# CAN_new_design.net
KiCad netlist of a schematic drawn in EAGLE
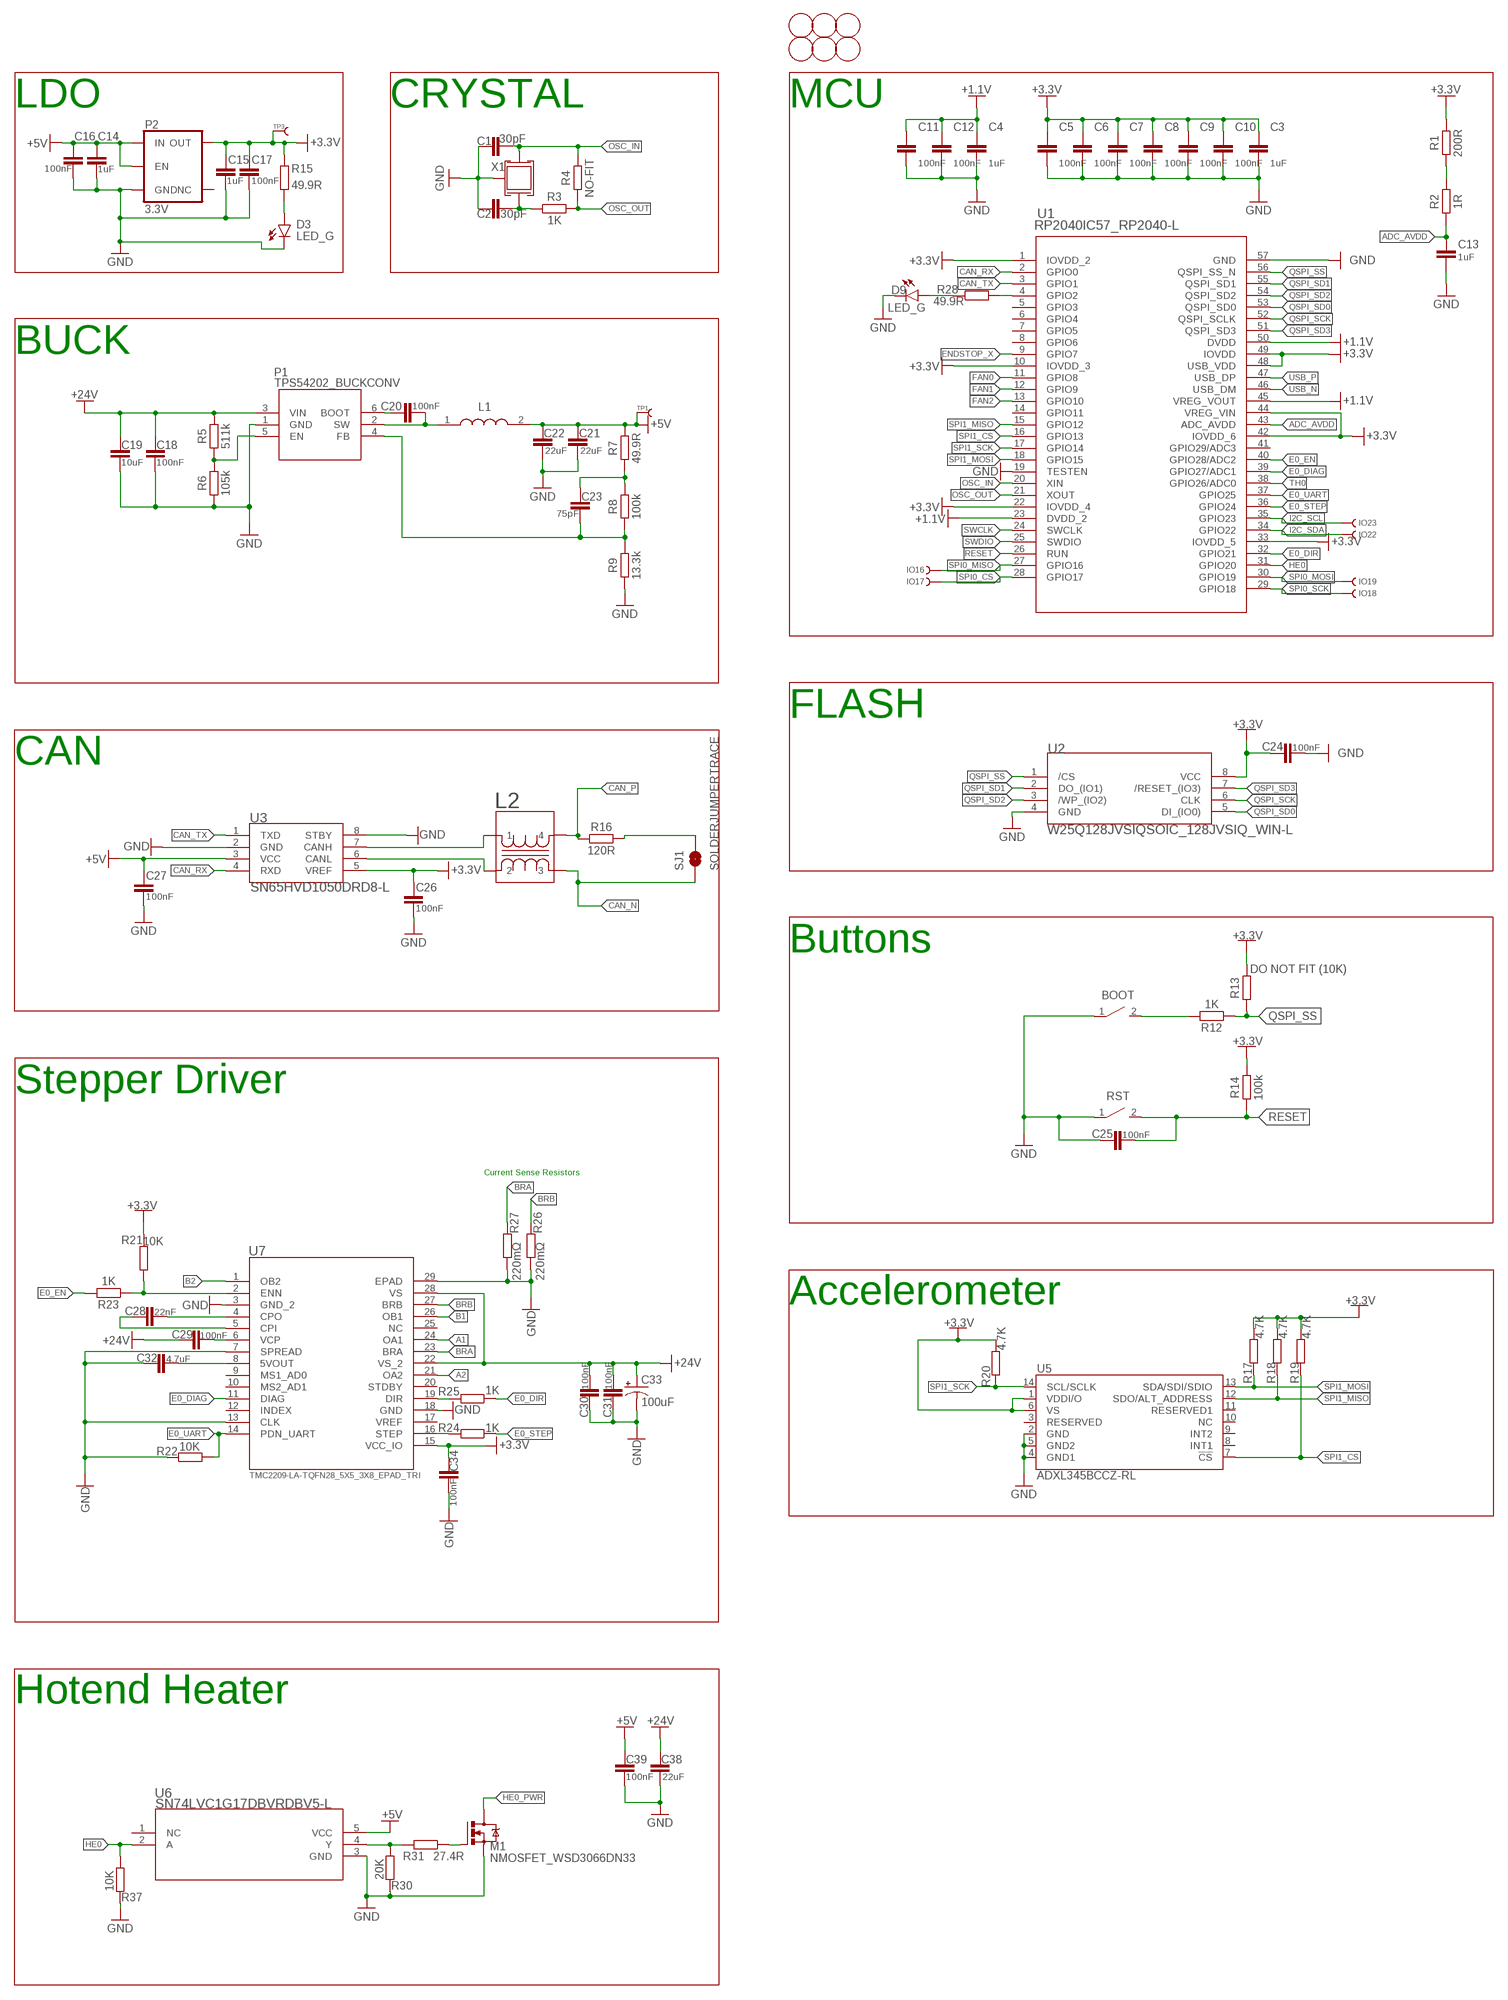
[diagram p0: schematic, sheet 1, part 1 of 2]
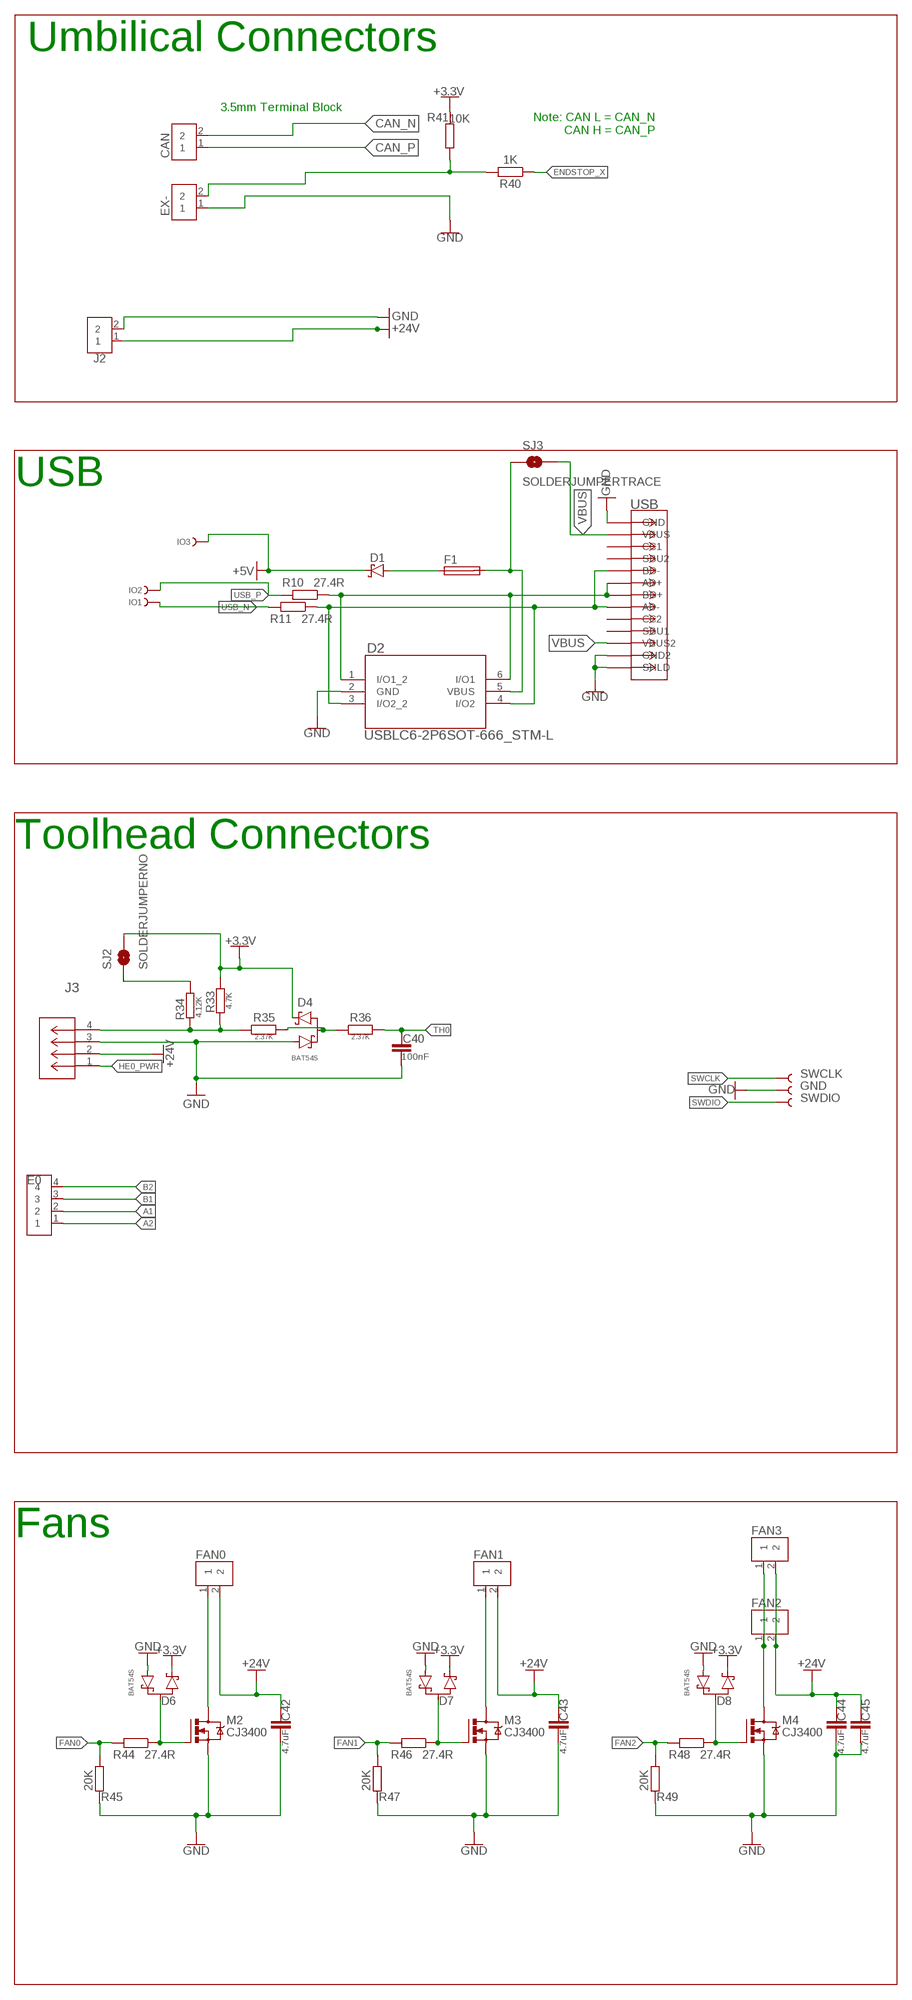
[diagram p1: schematic, sheet 1, part 2 of 2]

(export (version "E")
  (design (tool "Eeschema 10.0.6"))
  (components
    (comp (ref "BOOT")
      (value "B3U-1000P(M)-B")
      (footprint "eagle-import:B3U-1000P(M)-B")
      (fields (field (name "MANUFACTURER") "OMRON"))
      (libsource (lib "eagle-import") (part "B3U-X0001000P(M)-BB3U-1000P(M)-B"))
    )
    (comp (ref "C1")
      (value "30pF")
      (footprint "eagle-import:CAPC1005X60")
      (libsource (lib "eagle-import") (part "CCHIP-0402(1005-METRIC)_"))
    )
    (comp (ref "C2")
      (value "30pF")
      (footprint "eagle-import:CAPC1005X60")
      (libsource (lib "eagle-import") (part "CCHIP-0402(1005-METRIC)_"))
    )
    (comp (ref "C3")
      (value "1uF")
      (footprint "eagle-import:CAPC1005X60")
      (libsource (lib "eagle-import") (part "CCHIP-0402(1005-METRIC)_"))
    )
    (comp (ref "C4")
      (value "1uF")
      (footprint "eagle-import:CAPC1005X60")
      (libsource (lib "eagle-import") (part "CCHIP-0402(1005-METRIC)_"))
    )
    (comp (ref "C5")
      (value "100nF")
      (footprint "eagle-import:CAPC1005X60")
      (libsource (lib "eagle-import") (part "CCHIP-0402(1005-METRIC)_"))
    )
    (comp (ref "C6")
      (value "100nF")
      (footprint "eagle-import:CAPC1005X60")
      (libsource (lib "eagle-import") (part "CCHIP-0402(1005-METRIC)_"))
    )
    (comp (ref "C7")
      (value "100nF")
      (footprint "eagle-import:CAPC1005X60")
      (libsource (lib "eagle-import") (part "CCHIP-0402(1005-METRIC)_"))
    )
    (comp (ref "C8")
      (value "100nF")
      (footprint "eagle-import:CAPC1005X60")
      (libsource (lib "eagle-import") (part "CCHIP-0402(1005-METRIC)_"))
    )
    (comp (ref "C9")
      (value "100nF")
      (footprint "eagle-import:CAPC1005X60")
      (libsource (lib "eagle-import") (part "CCHIP-0402(1005-METRIC)_"))
    )
    (comp (ref "C10")
      (value "100nF")
      (footprint "eagle-import:CAPC1005X60")
      (libsource (lib "eagle-import") (part "CCHIP-0402(1005-METRIC)_"))
    )
    (comp (ref "C11")
      (value "100nF")
      (footprint "eagle-import:CAPC1005X60")
      (libsource (lib "eagle-import") (part "CCHIP-0402(1005-METRIC)_"))
    )
    (comp (ref "C12")
      (value "100nF")
      (footprint "eagle-import:CAPC1005X60")
      (libsource (lib "eagle-import") (part "CCHIP-0402(1005-METRIC)_"))
    )
    (comp (ref "C13")
      (value "1uF")
      (footprint "eagle-import:CAPC1005X60")
      (libsource (lib "eagle-import") (part "CCHIP-0402(1005-METRIC)_"))
    )
    (comp (ref "C14")
      (value "1uF")
      (footprint "eagle-import:CAPC1005X60")
      (libsource (lib "eagle-import") (part "CCHIP-0402(1005-METRIC)_"))
    )
    (comp (ref "C15")
      (value "1uF")
      (footprint "eagle-import:CAPC1005X60")
      (libsource (lib "eagle-import") (part "CCHIP-0402(1005-METRIC)_"))
    )
    (comp (ref "C16")
      (value "100nF")
      (footprint "eagle-import:CAPC1005X60")
      (libsource (lib "eagle-import") (part "CCHIP-0402(1005-METRIC)_"))
    )
    (comp (ref "C17")
      (value "100nF")
      (footprint "eagle-import:CAPC1005X60")
      (libsource (lib "eagle-import") (part "CCHIP-0402(1005-METRIC)_"))
    )
    (comp (ref "C18")
      (value "100nF")
      (footprint "eagle-import:CAPC1005X60")
      (libsource (lib "eagle-import") (part "CCHIP-0402(1005-METRIC)_"))
    )
    (comp (ref "C19")
      (value "10uF")
      (footprint "eagle-import:CAPC1608X85")
      (libsource (lib "eagle-import") (part "CCHIP-0603(1608-METRIC)_"))
    )
    (comp (ref "C20")
      (value "100nF")
      (footprint "eagle-import:CAPC1005X60")
      (libsource (lib "eagle-import") (part "CCHIP-0402(1005-METRIC)_"))
    )
    (comp (ref "C21")
      (value "22uF")
      (footprint "eagle-import:CAPC2012X110")
      (libsource (lib "eagle-import") (part "CCHIP-0805(2012-METRIC)_"))
    )
    (comp (ref "C22")
      (value "22uF")
      (footprint "eagle-import:CAPC2012X110")
      (libsource (lib "eagle-import") (part "CCHIP-0805(2012-METRIC)_"))
    )
    (comp (ref "C23")
      (value "75pF")
      (footprint "eagle-import:CAPC1005X60")
      (libsource (lib "eagle-import") (part "CCHIP-0402(1005-METRIC)_"))
    )
    (comp (ref "C24")
      (value "100nF")
      (footprint "eagle-import:CAPC1005X60")
      (libsource (lib "eagle-import") (part "CCHIP-0402(1005-METRIC)_"))
    )
    (comp (ref "C25")
      (value "100nF")
      (footprint "eagle-import:CAPC1005X60")
      (libsource (lib "eagle-import") (part "CCHIP-0402(1005-METRIC)_"))
    )
    (comp (ref "C26")
      (value "100nF")
      (footprint "eagle-import:CAPC1005X60")
      (libsource (lib "eagle-import") (part "CCHIP-0402(1005-METRIC)_"))
    )
    (comp (ref "C27")
      (value "100nF")
      (footprint "eagle-import:CAPC1005X60")
      (libsource (lib "eagle-import") (part "CCHIP-0402(1005-METRIC)_"))
    )
    (comp (ref "C28")
      (value "22nF")
      (footprint "eagle-import:CAPC1005X60")
      (libsource (lib "eagle-import") (part "CCHIP-0402(1005-METRIC)_"))
    )
    (comp (ref "C29")
      (value "100nF")
      (footprint "eagle-import:CAPC1005X60")
      (libsource (lib "eagle-import") (part "CCHIP-0402(1005-METRIC)_"))
    )
    (comp (ref "C30")
      (value "100nF")
      (footprint "eagle-import:CAPC1005X60")
      (libsource (lib "eagle-import") (part "CCHIP-0402(1005-METRIC)_"))
    )
    (comp (ref "C31")
      (value "100nF")
      (footprint "eagle-import:CAPC1005X60")
      (libsource (lib "eagle-import") (part "CCHIP-0402(1005-METRIC)_"))
    )
    (comp (ref "C32")
      (value "4.7uF")
      (footprint "eagle-import:CAPC1608X85")
      (libsource (lib "eagle-import") (part "CCHIP-0603(1608-METRIC)_"))
    )
    (comp (ref "C33")
      (value "100uF")
      (footprint "eagle-import:PANASONIC_D")
      (libsource (lib "eagle-import") (part "100UF-POLAR-25V-20%(ELEC)"))
    )
    (comp (ref "C34")
      (value "100nF")
      (footprint "eagle-import:CAPC1005X60")
      (libsource (lib "eagle-import") (part "CCHIP-0402(1005-METRIC)_"))
    )
    (comp (ref "C38")
      (value "22uF")
      (footprint "eagle-import:CAPC2012X110")
      (libsource (lib "eagle-import") (part "CCHIP-0805(2012-METRIC)_"))
    )
    (comp (ref "C39")
      (value "100nF")
      (footprint "eagle-import:CAPC1005X60")
      (libsource (lib "eagle-import") (part "CCHIP-0402(1005-METRIC)_"))
    )
    (comp (ref "C40")
      (value "100nF")
      (footprint "eagle-import:CAPC1005X60")
      (libsource (lib "eagle-import") (part "CCHIP-0402(1005-METRIC)_"))
    )
    (comp (ref "C42")
      (value "4.7uF")
      (footprint "eagle-import:CAPC1608X85")
      (libsource (lib "eagle-import") (part "CCHIP-0603(1608-METRIC)_"))
    )
    (comp (ref "C43")
      (value "4.7uF")
      (footprint "eagle-import:CAPC1608X85")
      (libsource (lib "eagle-import") (part "CCHIP-0603(1608-METRIC)_"))
    )
    (comp (ref "C44")
      (value "4.7uF")
      (footprint "eagle-import:CAPC1608X85")
      (libsource (lib "eagle-import") (part "CCHIP-0603(1608-METRIC)_"))
    )
    (comp (ref "C45")
      (value "4.7uF")
      (footprint "eagle-import:CAPC1608X85")
      (libsource (lib "eagle-import") (part "CCHIP-0603(1608-METRIC)_"))
    )
    (comp (ref "CAN")
      (value "3A/250V")
      (footprint "eagle-import:S2B-XH-A")
      (fields
        (field (name "DIGIKEY_PART_NUMBER") "455-2257-ND")
        (field (name "MANUFACTURER") "JST Sales America Inc.")
        (field (name "MPN") "S2B-XH-A(LF)(SN)")
        (field (name "CREATED_BY") "PCBLayout.com")
      )
      (libsource (lib "eagle-import") (part "S2B-XH-A"))
    )
    (comp (ref "D1")
      (value "MBR0520LT1G")
      (footprint "eagle-import:SODFL3718X115")
      (fields (field (name "MANUFACTURER") "ON Semiconductor"))
      (libsource (lib "eagle-import") (part "SCHOTTKY_DO-219MBR0520LT1G"))
    )
    (comp (ref "D2")
      (value "USBLC6-2P6SOT-666_STM-L")
      (footprint "eagle-import:SOT-666_STM-L")
      (fields
        (field (name "MANUFACTURER_PART_NUMBER") "USBLC6-2P6")
        (field (name "COPYRIGHT") "Copyright (C) 2023 Ultra Librarian. All rights reserved.")
      )
      (libsource (lib "eagle-import") (part "USBLC6-2P6SOT-666_STM-L"))
    )
    (comp (ref "D3")
      (value "LED_G")
      (footprint "eagle-import:LEDC1608X35N_FLAT-G")
      (libsource (lib "eagle-import") (part "CHIP-FLAT-G_0603-0.35MM"))
    )
    (comp (ref "D4")
      (value "BAT54S")
      (footprint "eagle-import:SOT23")
      (libsource (lib "eagle-import") (part "BAT54S"))
    )
    (comp (ref "D6")
      (value "BAT54S")
      (footprint "eagle-import:SOT23")
      (libsource (lib "eagle-import") (part "BAT54S"))
    )
    (comp (ref "D7")
      (value "BAT54S")
      (footprint "eagle-import:SOT23")
      (libsource (lib "eagle-import") (part "BAT54S"))
    )
    (comp (ref "D8")
      (value "BAT54S")
      (footprint "eagle-import:SOT23")
      (libsource (lib "eagle-import") (part "BAT54S"))
    )
    (comp (ref "D9")
      (value "LED_G")
      (footprint "eagle-import:LEDC1608X35N_FLAT-G")
      (libsource (lib "eagle-import") (part "CHIP-FLAT-G_0603-0.35MM"))
    )
    (comp (ref "E0")
      (value "3A/250V")
      (footprint "eagle-import:S4B-XH-A")
      (fields (field (name "MANUFACTURER") "JST Sales America Inc. ") (field (name "MPN") "S4B-XH-A(LF)(SN)"))
      (libsource (lib "eagle-import") (part "S4B-XH-A"))
    )
    (comp (ref "EX-")
      (value "3A/250V")
      (footprint "eagle-import:S2B-XH-A")
      (fields
        (field (name "DIGIKEY_PART_NUMBER") "455-2257-ND")
        (field (name "MANUFACTURER") "JST Sales America Inc.")
        (field (name "MPN") "S2B-XH-A(LF)(SN)")
        (field (name "CREATED_BY") "PCBLayout.com")
      )
      (libsource (lib "eagle-import") (part "S2B-XH-A"))
    )
    (comp (ref "F1")
      (value "FUSE_CHIP-0603(1608-METRIC)")
      (footprint "eagle-import:FUSC1608X60N")
      (libsource (lib "eagle-import") (part "FUSECHIP-0603(1608-METRIC)_"))
    )
    (comp (ref "FAN0")
      (value "3A/250V")
      (footprint "eagle-import:S2B-XH-A")
      (fields
        (field (name "DIGIKEY_PART_NUMBER") "455-2257-ND")
        (field (name "MANUFACTURER") "JST Sales America Inc.")
        (field (name "MPN") "S2B-XH-A(LF)(SN)")
        (field (name "CREATED_BY") "PCBLayout.com")
      )
      (libsource (lib "eagle-import") (part "S2B-XH-A"))
    )
    (comp (ref "FAN1")
      (value "3A/250V")
      (footprint "eagle-import:S2B-XH-A")
      (fields
        (field (name "DIGIKEY_PART_NUMBER") "455-2257-ND")
        (field (name "MANUFACTURER") "JST Sales America Inc.")
        (field (name "MPN") "S2B-XH-A(LF)(SN)")
        (field (name "CREATED_BY") "PCBLayout.com")
      )
      (libsource (lib "eagle-import") (part "S2B-XH-A"))
    )
    (comp (ref "FAN2")
      (value "3A/250V")
      (footprint "eagle-import:S2B-XH-A")
      (fields
        (field (name "DIGIKEY_PART_NUMBER") "455-2257-ND")
        (field (name "MANUFACTURER") "JST Sales America Inc.")
        (field (name "MPN") "S2B-XH-A(LF)(SN)")
        (field (name "CREATED_BY") "PCBLayout.com")
      )
      (libsource (lib "eagle-import") (part "S2B-XH-A"))
    )
    (comp (ref "FAN3")
      (value "3A/250V")
      (footprint "eagle-import:S2B-XH-A")
      (fields
        (field (name "DIGIKEY_PART_NUMBER") "455-2257-ND")
        (field (name "MANUFACTURER") "JST Sales America Inc.")
        (field (name "MPN") "S2B-XH-A(LF)(SN)")
        (field (name "CREATED_BY") "PCBLayout.com")
      )
      (libsource (lib "eagle-import") (part "S2B-XH-A"))
    )
    (comp (ref "FD1")
      (value "FIDUCIAL")
      (footprint "eagle-import:FIDUCIAL_1MM")
      (libsource (lib "eagle-import") (part "FIDUCIAL"))
    )
    (comp (ref "FD2")
      (value "FIDUCIAL")
      (footprint "eagle-import:FIDUCIAL_1MM")
      (libsource (lib "eagle-import") (part "FIDUCIAL"))
    )
    (comp (ref "FD3")
      (value "FIDUCIAL")
      (footprint "eagle-import:FIDUCIAL_1MM")
      (libsource (lib "eagle-import") (part "FIDUCIAL"))
    )
    (comp (ref "FD4")
      (value "FIDUCIAL")
      (footprint "eagle-import:FIDUCIAL_1MM")
      (libsource (lib "eagle-import") (part "FIDUCIAL"))
    )
    (comp (ref "FD5")
      (value "FIDUCIAL")
      (footprint "eagle-import:FIDUCIAL_1MM")
      (libsource (lib "eagle-import") (part "FIDUCIAL"))
    )
    (comp (ref "FD6")
      (value "FIDUCIAL")
      (footprint "eagle-import:FIDUCIAL_1MM")
      (libsource (lib "eagle-import") (part "FIDUCIAL"))
    )
    (comp (ref "GND")
      (value "TEST-POINT3X4")
      (footprint "eagle-import:PAD.03X.04")
      (libsource (lib "eagle-import") (part "SparkFun-Connectors_513_TEST-POINT3X4"))
    )
    (comp (ref "IO1")
      (value "TEST-POINT3")
      (footprint "eagle-import:PAD.03X.03")
      (libsource (lib "eagle-import") (part "SparkFun-Connectors_513_TEST-POINT3"))
    )
    (comp (ref "IO2")
      (value "TEST-POINT3")
      (footprint "eagle-import:PAD.03X.03")
      (libsource (lib "eagle-import") (part "SparkFun-Connectors_513_TEST-POINT3"))
    )
    (comp (ref "IO3")
      (value "TEST-POINT3")
      (footprint "eagle-import:PAD.03X.03")
      (libsource (lib "eagle-import") (part "SparkFun-Connectors_513_TEST-POINT3"))
    )
    (comp (ref "IO16")
      (value "TEST-POINT3")
      (footprint "eagle-import:PAD.03X.03")
      (libsource (lib "eagle-import") (part "SparkFun-Connectors_513_TEST-POINT3"))
    )
    (comp (ref "IO17")
      (value "TEST-POINT3")
      (footprint "eagle-import:PAD.03X.03")
      (libsource (lib "eagle-import") (part "SparkFun-Connectors_513_TEST-POINT3"))
    )
    (comp (ref "IO18")
      (value "TEST-POINT3")
      (footprint "eagle-import:PAD.03X.03")
      (libsource (lib "eagle-import") (part "SparkFun-Connectors_513_TEST-POINT3"))
    )
    (comp (ref "IO19")
      (value "TEST-POINT3")
      (footprint "eagle-import:PAD.03X.03")
      (libsource (lib "eagle-import") (part "SparkFun-Connectors_513_TEST-POINT3"))
    )
    (comp (ref "IO22")
      (value "TEST-POINT3")
      (footprint "eagle-import:PAD.03X.03")
      (libsource (lib "eagle-import") (part "SparkFun-Connectors_513_TEST-POINT3"))
    )
    (comp (ref "IO23")
      (value "TEST-POINT3")
      (footprint "eagle-import:PAD.03X.03")
      (libsource (lib "eagle-import") (part "SparkFun-Connectors_513_TEST-POINT3"))
    )
    (comp (ref "J2")
      (value "2828XX-2282837-2")
      (footprint "eagle-import:TERMBLK_508-2N")
      (fields (field (name "MANUFACTURER") "TE Connectivity") (field (name "MPN") "282837-2"))
      (libsource (lib "eagle-import") (part "2828XX-2282837-2"))
    )
    (comp (ref "J3")
      (value "430450400CON_430450400_MOL")
      (footprint "eagle-import:CON_430450400_MOL")
      (fields
        (field (name "MANUFACTURER_PART_NUMBER") "430450400")
        (field (name "COPYRIGHT") "Copyright (C) 2023 Ultra Librarian. All rights reserved.")
      )
      (libsource (lib "eagle-import") (part "430450400CON_430450400_MOL"))
    )
    (comp (ref "L1")
      (value "ASPI-0630HI-100M-T157X7X4")
      (footprint "eagle-import:SMDRI74-680MT")
      (libsource (lib "eagle-import") (part "ASPI-0630HI-100M-T157X7X4"))
    )
    (comp (ref "L2")
      (value "ACM2012-201-2P-T002ACM2012_TDK")
      (footprint "eagle-import:ACM2012_TDK")
      (fields
        (field (name "MANUFACTURER_PART_NUMBER") "ACM2012-201-2P-T002")
        (field (name "COPYRIGHT") "Copyright (C) 2023 Ultra Librarian. All rights reserved.")
      )
      (libsource (lib "eagle-import") (part "ACM2012-201-2P-T002ACM2012_TDK"))
    )
    (comp (ref "M1")
      (value "NMOSFET_WSD3066DN33")
      (footprint "eagle-import:NMOSFET_WSD3066DN33")
      (libsource (lib "eagle-import") (part "NMOSFET_WSD3066DN33"))
    )
    (comp (ref "M2")
      (value "CJ3400")
      (footprint "eagle-import:SOT23")
      (fields (field (name "MANUFACTURER") "ON Semiconductor") (field (name "MPN") "BSS123L"))
      (libsource (lib "eagle-import") (part "NMOSFET__SOT23-GSDBSS123"))
    )
    (comp (ref "M3")
      (value "CJ3400")
      (footprint "eagle-import:SOT23")
      (fields (field (name "MANUFACTURER") "ON Semiconductor") (field (name "MPN") "BSS123L"))
      (libsource (lib "eagle-import") (part "NMOSFET__SOT23-GSDBSS123"))
    )
    (comp (ref "M4")
      (value "CJ3400")
      (footprint "eagle-import:SOT23")
      (fields (field (name "MANUFACTURER") "ON Semiconductor") (field (name "MPN") "BSS123L"))
      (libsource (lib "eagle-import") (part "NMOSFET__SOT23-GSDBSS123"))
    )
    (comp (ref "P1")
      (value "TPS54202_BUCKCONV")
      (footprint "eagle-import:SOT-23-6")
      (libsource (lib "eagle-import") (part "TPS54202_BUCKCONV"))
    )
    (comp (ref "P2")
      (value "3.3V")
      (footprint "eagle-import:SOT23-5")
      (libsource (lib "eagle-import") (part "V_REG_AP2112K-3.3V"))
    )
    (comp (ref "R1")
      (value "200R")
      (footprint "eagle-import:RESC1005X40")
      (libsource (lib "eagle-import") (part "RCHIP-0402(1005-METRIC)_"))
    )
    (comp (ref "R2")
      (value "1R")
      (footprint "eagle-import:RESC1005X40")
      (libsource (lib "eagle-import") (part "RCHIP-0402(1005-METRIC)_"))
    )
    (comp (ref "R3")
      (value "1K")
      (footprint "eagle-import:RESC1005X40")
      (libsource (lib "eagle-import") (part "RCHIP-0402(1005-METRIC)_"))
    )
    (comp (ref "R4")
      (value "NO-FIT")
      (footprint "eagle-import:RESC1005X40")
      (libsource (lib "eagle-import") (part "RCHIP-0402(1005-METRIC)_"))
    )
    (comp (ref "R5")
      (value "511k")
      (footprint "eagle-import:RESC1005X40")
      (libsource (lib "eagle-import") (part "RCHIP-0402(1005-METRIC)_"))
    )
    (comp (ref "R6")
      (value "105k")
      (footprint "eagle-import:RESC1005X40")
      (libsource (lib "eagle-import") (part "RCHIP-0402(1005-METRIC)_"))
    )
    (comp (ref "R7")
      (value "49.9R")
      (footprint "eagle-import:RESC1005X40")
      (libsource (lib "eagle-import") (part "RCHIP-0402(1005-METRIC)_"))
    )
    (comp (ref "R8")
      (value "100k")
      (footprint "eagle-import:RESC1005X40")
      (libsource (lib "eagle-import") (part "RCHIP-0402(1005-METRIC)_"))
    )
    (comp (ref "R9")
      (value "13.3k")
      (footprint "eagle-import:RESC1005X40")
      (libsource (lib "eagle-import") (part "RCHIP-0402(1005-METRIC)_"))
    )
    (comp (ref "R10")
      (value "27.4R")
      (footprint "eagle-import:RESC1005X40")
      (libsource (lib "eagle-import") (part "RCHIP-0402(1005-METRIC)_"))
    )
    (comp (ref "R11")
      (value "27.4R")
      (footprint "eagle-import:RESC1005X40")
      (libsource (lib "eagle-import") (part "RCHIP-0402(1005-METRIC)_"))
    )
    (comp (ref "R12")
      (value "1K")
      (footprint "eagle-import:RESC1005X40")
      (libsource (lib "eagle-import") (part "RCHIP-0402(1005-METRIC)_"))
    )
    (comp (ref "R13")
      (value "DO NOT FIT (10K)")
      (footprint "eagle-import:RESC1005X40")
      (libsource (lib "eagle-import") (part "RCHIP-0402(1005-METRIC)_"))
    )
    (comp (ref "R14")
      (value "100k")
      (footprint "eagle-import:RESC1005X40")
      (libsource (lib "eagle-import") (part "RCHIP-0402(1005-METRIC)_"))
    )
    (comp (ref "R15")
      (value "49.9R")
      (footprint "eagle-import:RESC1005X40")
      (libsource (lib "eagle-import") (part "RCHIP-0402(1005-METRIC)_"))
    )
    (comp (ref "R16")
      (value "120R")
      (footprint "eagle-import:RESC1005X40")
      (libsource (lib "eagle-import") (part "RCHIP-0402(1005-METRIC)_"))
    )
    (comp (ref "R17")
      (value "4.7K")
      (footprint "eagle-import:RESC1005X40")
      (libsource (lib "eagle-import") (part "RCHIP-0402(1005-METRIC)_"))
    )
    (comp (ref "R18")
      (value "4.7K")
      (footprint "eagle-import:RESC1005X40")
      (libsource (lib "eagle-import") (part "RCHIP-0402(1005-METRIC)_"))
    )
    (comp (ref "R19")
      (value "4.7K")
      (footprint "eagle-import:RESC1005X40")
      (libsource (lib "eagle-import") (part "RCHIP-0402(1005-METRIC)_"))
    )
    (comp (ref "R20")
      (value "4.7K")
      (footprint "eagle-import:RESC1005X40")
      (libsource (lib "eagle-import") (part "RCHIP-0402(1005-METRIC)_"))
    )
    (comp (ref "R21")
      (value "10K")
      (footprint "eagle-import:RESC1005X40")
      (libsource (lib "eagle-import") (part "RCHIP-0402(1005-METRIC)_"))
    )
    (comp (ref "R22")
      (value "10K")
      (footprint "eagle-import:RESC1005X40")
      (libsource (lib "eagle-import") (part "RCHIP-0402(1005-METRIC)_"))
    )
    (comp (ref "R23")
      (value "1K")
      (footprint "eagle-import:RESC1005X40")
      (libsource (lib "eagle-import") (part "RCHIP-0402(1005-METRIC)_"))
    )
    (comp (ref "R24")
      (value "1K")
      (footprint "eagle-import:RESC1005X40")
      (libsource (lib "eagle-import") (part "RCHIP-0402(1005-METRIC)_"))
    )
    (comp (ref "R25")
      (value "1K")
      (footprint "eagle-import:RESC1005X40")
      (libsource (lib "eagle-import") (part "RCHIP-0402(1005-METRIC)_"))
    )
    (comp (ref "R26")
      (value "220mΩ")
      (footprint "eagle-import:RESC1005X40")
      (libsource (lib "eagle-import") (part "RCHIP-0402(1005-METRIC)_"))
    )
    (comp (ref "R27")
      (value "220mΩ")
      (footprint "eagle-import:RESC1005X40")
      (libsource (lib "eagle-import") (part "RCHIP-0402(1005-METRIC)_"))
    )
    (comp (ref "R28")
      (value "49.9R")
      (footprint "eagle-import:RESC1005X40")
      (libsource (lib "eagle-import") (part "RCHIP-0402(1005-METRIC)_"))
    )
    (comp (ref "R30")
      (value "20K")
      (footprint "eagle-import:RESC1005X40")
      (libsource (lib "eagle-import") (part "RCHIP-0402(1005-METRIC)_"))
    )
    (comp (ref "R31")
      (value "27.4R")
      (footprint "eagle-import:RESC1005X40")
      (libsource (lib "eagle-import") (part "RCHIP-0402(1005-METRIC)_"))
    )
    (comp (ref "R33")
      (value "4.7K")
      (footprint "eagle-import:RESC1005X40")
      (libsource (lib "eagle-import") (part "RCHIP-0402(1005-METRIC)_"))
    )
    (comp (ref "R34")
      (value "4.12K")
      (footprint "eagle-import:RESC1005X40")
      (libsource (lib "eagle-import") (part "RCHIP-0402(1005-METRIC)_"))
    )
    (comp (ref "R35")
      (value "2.37K")
      (footprint "eagle-import:RESC1005X40")
      (libsource (lib "eagle-import") (part "RCHIP-0402(1005-METRIC)_"))
    )
    (comp (ref "R36")
      (value "2.37K")
      (footprint "eagle-import:RESC1005X40")
      (libsource (lib "eagle-import") (part "RCHIP-0402(1005-METRIC)_"))
    )
    (comp (ref "R37")
      (value "10K")
      (footprint "eagle-import:RESC1005X40")
      (libsource (lib "eagle-import") (part "RCHIP-0402(1005-METRIC)_"))
    )
    (comp (ref "R40")
      (value "1K")
      (footprint "eagle-import:RESC1005X40")
      (libsource (lib "eagle-import") (part "RCHIP-0402(1005-METRIC)_"))
    )
    (comp (ref "R41")
      (value "10K")
      (footprint "eagle-import:RESC1005X40")
      (libsource (lib "eagle-import") (part "RCHIP-0402(1005-METRIC)_"))
    )
    (comp (ref "R44")
      (value "27.4R")
      (footprint "eagle-import:RESC1005X40")
      (libsource (lib "eagle-import") (part "RCHIP-0402(1005-METRIC)_"))
    )
    (comp (ref "R45")
      (value "20K")
      (footprint "eagle-import:RESC1005X40")
      (libsource (lib "eagle-import") (part "RCHIP-0402(1005-METRIC)_"))
    )
    (comp (ref "R46")
      (value "27.4R")
      (footprint "eagle-import:RESC1005X40")
      (libsource (lib "eagle-import") (part "RCHIP-0402(1005-METRIC)_"))
    )
    (comp (ref "R47")
      (value "20K")
      (footprint "eagle-import:RESC1005X40")
      (libsource (lib "eagle-import") (part "RCHIP-0402(1005-METRIC)_"))
    )
    (comp (ref "R48")
      (value "27.4R")
      (footprint "eagle-import:RESC1005X40")
      (libsource (lib "eagle-import") (part "RCHIP-0402(1005-METRIC)_"))
    )
    (comp (ref "R49")
      (value "20K")
      (footprint "eagle-import:RESC1005X40")
      (libsource (lib "eagle-import") (part "RCHIP-0402(1005-METRIC)_"))
    )
    (comp (ref "RST")
      (value "B3U-1000P(M)-B")
      (footprint "eagle-import:B3U-1000P(M)-B")
      (fields (field (name "MANUFACTURER") "OMRON"))
      (libsource (lib "eagle-import") (part "B3U-X0001000P(M)-BB3U-1000P(M)-B"))
    )
    (comp (ref "SJ1")
      (value "SOLDERJUMPERTRACE")
      (footprint "eagle-import:SJ_2S-TRACE")
      (libsource (lib "eagle-import") (part "SOLDERJUMPERTRACE"))
    )
    (comp (ref "SJ2")
      (value "SOLDERJUMPERNO")
      (footprint "eagle-import:SJ_2S-NO")
      (libsource (lib "eagle-import") (part "SOLDERJUMPERNO"))
    )
    (comp (ref "SJ3")
      (value "SOLDERJUMPERTRACE")
      (footprint "eagle-import:SJ_2S-TRACE")
      (libsource (lib "eagle-import") (part "SOLDERJUMPERTRACE"))
    )
    (comp (ref "SWCLK")
      (value "TEST-POINT3X4")
      (footprint "eagle-import:PAD.03X.04")
      (libsource (lib "eagle-import") (part "SparkFun-Connectors_513_TEST-POINT3X4"))
    )
    (comp (ref "SWDIO")
      (value "TEST-POINT3X4")
      (footprint "eagle-import:PAD.03X.04")
      (libsource (lib "eagle-import") (part "SparkFun-Connectors_513_TEST-POINT3X4"))
    )
    (comp (ref "TP1")
      (value "TEST-POINT3")
      (footprint "eagle-import:PAD.012X.012")
      (libsource (lib "eagle-import") (part "TEST-POINT3"))
    )
    (comp (ref "TP3")
      (value "TEST-POINT3")
      (footprint "eagle-import:PAD.012X.012")
      (libsource (lib "eagle-import") (part "TEST-POINT3"))
    )
    (comp (ref "U1")
      (value "RP2040IC57_RP2040-L")
      (footprint "eagle-import:IC57_RP2040-L")
      (fields
        (field (name "MANUFACTURER_PART_NUMBER") "RP2040")
        (field (name "COPYRIGHT") "Copyright (C) 2023 Ultra Librarian. All rights reserved.")
      )
      (libsource (lib "eagle-import") (part "RP2040IC57_RP2040-L"))
    )
    (comp (ref "U2")
      (value "W25Q128JVSIQSOIC_128JVSIQ_WIN-L")
      (footprint "eagle-import:SOIC_128JVSIQ_WIN-L")
      (fields
        (field (name "MANUFACTURER_PART_NUMBER") "W25Q128JVSIQ")
        (field (name "COPYRIGHT") "Copyright (C) 2023 Ultra Librarian. All rights reserved.")
      )
      (libsource (lib "eagle-import") (part "W25Q128JVSIQSOIC_128JVSIQ_WIN-L"))
    )
    (comp (ref "U3")
      (value "SN65HVD1050DRD8-L")
      (footprint "eagle-import:D8-L")
      (fields
        (field (name "MANUFACTURER_PART_NUMBER") "SN65HVD1050DR")
        (field (name "COPYRIGHT") "Copyright (C) 2023 Ultra Librarian. All rights reserved.")
      )
      (libsource (lib "eagle-import") (part "SN65HVD1050DRD8-L"))
    )
    (comp (ref "U5")
      (value "ADXL345BCCZ-RL")
      (footprint "eagle-import:ADXL345_LGA14")
      (fields (field (name "MANUFACTURER") "ANALOG DEVICES"))
      (libsource (lib "eagle-import") (part "ADXL345BCCZ-RL"))
    )
    (comp (ref "U6")
      (value "SN74LVC1G17DBVRDBV5-L")
      (footprint "eagle-import:DBV5-L")
      (fields
        (field (name "MANUFACTURER_PART_NUMBER") "SN74LVC1G17DBVR")
        (field (name "COPYRIGHT") "Copyright (C) 2023 Ultra Librarian. All rights reserved.")
      )
      (libsource (lib "eagle-import") (part "SN74LVC1G17DBVRDBV5-L"))
    )
    (comp (ref "U7")
      (value "TMC2209-LA-TQFN28_5X5_3X8_EPAD_TRI")
      (footprint "eagle-import:QFN28_5X5_3X8_EPAD_TRI")
      (fields
        (field (name "MANUFACTURER_PART_NUMBER") "TMC2209-LA-T")
        (field (name "COPYRIGHT") "Copyright (C) 2023 Ultra Librarian. All rights reserved.")
      )
      (libsource (lib "eagle-import") (part "TMC2209-LA-TQFN28_5X5_3X8_EPAD_TRI"))
    )
    (comp (ref "USB")
      (value "USB-C(DX07S016JA1R1500)")
      (footprint "eagle-import:CONN12_016JA1R1500_JAE")
      (fields
        (field (name "MANUFACTURER_PART_NUMBER") "DX07S016JA1R1500")
        (field (name "COPYRIGHT") "Copyright (C) 2018 Accelerated Designs. All rights reserved")
      )
      (libsource (lib "eagle-import") (part "USB-C(DX07S016JA1R1500)"))
    )
    (comp (ref "X1")
      (value "CRYSTAL_TAXM12M4RLBDDT2T_3225")
      (footprint "eagle-import:CRYSTAL_3225")
      (libsource (lib "eagle-import") (part "CRYSTAL_TAXM12M4RLBDDT2T_3225"))
    )
  )
  (nets
    (net (code "1") (name "+1.1V") (class "Default")
      (node (ref "C11") (pin "1") (pinfunction "1_1") (pintype "passive"))
      (node (ref "C12") (pin "1") (pinfunction "1_1") (pintype "passive"))
      (node (ref "C4") (pin "1") (pinfunction "1_1") (pintype "passive"))
      (node (ref "U1") (pin "23") (pinfunction "DVDD_2_23") (pintype "power_in"))
      (node (ref "U1") (pin "45") (pinfunction "VREG_VOUT_45") (pintype "output"))
      (node (ref "U1") (pin "50") (pinfunction "DVDD_50") (pintype "power_in"))
    )
    (net (code "2") (name "+3.3V") (class "Default")
      (node (ref "C10") (pin "1") (pinfunction "1_1") (pintype "passive"))
      (node (ref "C15") (pin "1") (pinfunction "1_1") (pintype "passive"))
      (node (ref "C17") (pin "1") (pinfunction "1_1") (pintype "passive"))
      (node (ref "C24") (pin "1") (pinfunction "1_1") (pintype "passive"))
      (node (ref "C26") (pin "1") (pinfunction "1_1") (pintype "passive"))
      (node (ref "C3") (pin "1") (pinfunction "1_1") (pintype "passive"))
      (node (ref "C34") (pin "1") (pinfunction "1_1") (pintype "passive"))
      (node (ref "C5") (pin "1") (pinfunction "1_1") (pintype "passive"))
      (node (ref "C6") (pin "1") (pinfunction "1_1") (pintype "passive"))
      (node (ref "C7") (pin "1") (pinfunction "1_1") (pintype "passive"))
      (node (ref "C8") (pin "1") (pinfunction "1_1") (pintype "passive"))
      (node (ref "C9") (pin "1") (pinfunction "1_1") (pintype "passive"))
      (node (ref "D4") (pin "2") (pinfunction "2_2") (pintype "passive"))
      (node (ref "D6") (pin "2") (pinfunction "2_2") (pintype "passive"))
      (node (ref "D7") (pin "2") (pinfunction "2_2") (pintype "passive"))
      (node (ref "D8") (pin "2") (pinfunction "2_2") (pintype "passive"))
      (node (ref "P2") (pin "5") (pinfunction "OUT_5") (pintype "passive"))
      (node (ref "R1") (pin "2") (pinfunction "2_2") (pintype "passive"))
      (node (ref "R13") (pin "2") (pinfunction "2_2") (pintype "passive"))
      (node (ref "R14") (pin "2") (pinfunction "2_2") (pintype "passive"))
      (node (ref "R15") (pin "2") (pinfunction "2_2") (pintype "passive"))
      (node (ref "R17") (pin "2") (pinfunction "2_2") (pintype "passive"))
      (node (ref "R18") (pin "2") (pinfunction "2_2") (pintype "passive"))
      (node (ref "R19") (pin "2") (pinfunction "2_2") (pintype "passive"))
      (node (ref "R20") (pin "2") (pinfunction "2_2") (pintype "passive"))
      (node (ref "R21") (pin "1") (pinfunction "1_1") (pintype "passive"))
      (node (ref "R33") (pin "2") (pinfunction "2_2") (pintype "passive"))
      (node (ref "R41") (pin "1") (pinfunction "1_1") (pintype "passive"))
      (node (ref "SJ2") (pin "2") (pinfunction "2_2") (pintype "passive"))
      (node (ref "TP3") (pin "P$1") (pinfunction "1_P$1") (pintype "bidirectional"))
      (node (ref "U1") (pin "1") (pinfunction "IOVDD_2_1") (pintype "power_in"))
      (node (ref "U1") (pin "10") (pinfunction "IOVDD_3_10") (pintype "power_in"))
      (node (ref "U1") (pin "22") (pinfunction "IOVDD_4_22") (pintype "power_in"))
      (node (ref "U1") (pin "33") (pinfunction "IOVDD_5_33") (pintype "power_in"))
      (node (ref "U1") (pin "42") (pinfunction "IOVDD_6_42") (pintype "power_in"))
      (node (ref "U1") (pin "44") (pinfunction "VREG_VIN_44") (pintype "passive"))
      (node (ref "U1") (pin "48") (pinfunction "USB_VDD_48") (pintype "power_in"))
      (node (ref "U1") (pin "49") (pinfunction "IOVDD_49") (pintype "power_in"))
      (node (ref "U2") (pin "8") (pinfunction "VCC_8") (pintype "power_in"))
      (node (ref "U3") (pin "5") (pinfunction "VREF_5") (pintype "power_in"))
      (node (ref "U5") (pin "1") (pinfunction "VDDI/O_1") (pintype "bidirectional"))
      (node (ref "U5") (pin "6") (pinfunction "VS_6") (pintype "bidirectional"))
      (node (ref "U7") (pin "15") (pinfunction "VCC_IO_15") (pintype "power_in"))
    )
    (net (code "3") (name "+5V") (class "Default")
      (node (ref "C14") (pin "1") (pinfunction "1_1") (pintype "passive"))
      (node (ref "C16") (pin "1") (pinfunction "1_1") (pintype "passive"))
      (node (ref "C21") (pin "1") (pinfunction "1_1") (pintype "passive"))
      (node (ref "C22") (pin "1") (pinfunction "1_1") (pintype "passive"))
      (node (ref "C27") (pin "1") (pinfunction "1_1") (pintype "passive"))
      (node (ref "C39") (pin "1") (pinfunction "1_1") (pintype "passive"))
      (node (ref "D1") (pin "1") (pinfunction "C_1") (pintype "passive"))
      (node (ref "IO3") (pin "P$1") (pinfunction "1_P$1") (pintype "bidirectional"))
      (node (ref "L1") (pin "2") (pinfunction "2_2") (pintype "bidirectional"))
      (node (ref "P2") (pin "1") (pinfunction "IN_1") (pintype "input"))
      (node (ref "P2") (pin "3") (pinfunction "EN_3") (pintype "input"))
      (node (ref "R7") (pin "2") (pinfunction "2_2") (pintype "passive"))
      (node (ref "TP1") (pin "P$1") (pinfunction "1_P$1") (pintype "bidirectional"))
      (node (ref "U3") (pin "3") (pinfunction "VCC_3") (pintype "power_in"))
      (node (ref "U6") (pin "5") (pinfunction "VCC_5") (pintype "power_in"))
    )
    (net (code "4") (name "+24V") (class "Default")
      (node (ref "C18") (pin "1") (pinfunction "1_1") (pintype "passive"))
      (node (ref "C19") (pin "1") (pinfunction "1_1") (pintype "passive"))
      (node (ref "C29") (pin "1") (pinfunction "1_1") (pintype "passive"))
      (node (ref "C30") (pin "2") (pinfunction "2_2") (pintype "passive"))
      (node (ref "C31") (pin "2") (pinfunction "2_2") (pintype "passive"))
      (node (ref "C33") (pin "+") (pinfunction "+_+") (pintype "passive"))
      (node (ref "C38") (pin "1") (pinfunction "1_1") (pintype "passive"))
      (node (ref "C42") (pin "1") (pinfunction "1_1") (pintype "passive"))
      (node (ref "C43") (pin "1") (pinfunction "1_1") (pintype "passive"))
      (node (ref "C44") (pin "1") (pinfunction "1_1") (pintype "passive"))
      (node (ref "C45") (pin "1") (pinfunction "1_1") (pintype "passive"))
      (node (ref "FAN0") (pin "2") (pinfunction "2_2") (pintype "bidirectional"))
      (node (ref "FAN1") (pin "2") (pinfunction "2_2") (pintype "bidirectional"))
      (node (ref "J2") (pin "1") (pinfunction "1_1") (pintype "bidirectional"))
      (node (ref "J3") (pin "2") (pinfunction "2_2") (pintype "passive"))
      (node (ref "P1") (pin "3") (pinfunction "VIN_3") (pintype "bidirectional"))
      (node (ref "R5") (pin "2") (pinfunction "2_2") (pintype "passive"))
      (node (ref "U7") (pin "22") (pinfunction "VS_2_22") (pintype "power_in"))
      (node (ref "U7") (pin "28") (pinfunction "VS_28") (pintype "power_in"))
    )
    (net (code "5") (name "A1") (class "Default")
      (node (ref "E0") (pin "2") (pinfunction "2_2") (pintype "bidirectional"))
      (node (ref "U7") (pin "24") (pinfunction "OA1_24") (pintype "output"))
    )
    (net (code "6") (name "A2") (class "Default")
      (node (ref "E0") (pin "1") (pinfunction "1_1") (pintype "bidirectional"))
      (node (ref "U7") (pin "21") (pinfunction "OA2_21") (pintype "output"))
    )
    (net (code "7") (name "ADC_AVDD") (class "Default")
      (node (ref "C13") (pin "1") (pinfunction "1_1") (pintype "passive"))
      (node (ref "R2") (pin "1") (pinfunction "1_1") (pintype "passive"))
      (node (ref "U1") (pin "43") (pinfunction "ADC_AVDD_43") (pintype "power_in"))
    )
    (net (code "8") (name "B1") (class "Default")
      (node (ref "E0") (pin "3") (pinfunction "3_3") (pintype "bidirectional"))
      (node (ref "U7") (pin "26") (pinfunction "OB1_26") (pintype "output"))
    )
    (net (code "9") (name "B2") (class "Default")
      (node (ref "E0") (pin "4") (pinfunction "4_4") (pintype "bidirectional"))
      (node (ref "U7") (pin "1") (pinfunction "OB2_1") (pintype "output"))
    )
    (net (code "10") (name "BRA") (class "Default")
      (node (ref "R27") (pin "2") (pinfunction "2_2") (pintype "passive"))
      (node (ref "U7") (pin "23") (pinfunction "BRA_23") (pintype "passive"))
    )
    (net (code "11") (name "BRB") (class "Default")
      (node (ref "R26") (pin "2") (pinfunction "2_2") (pintype "passive"))
      (node (ref "U7") (pin "27") (pinfunction "BRB_27") (pintype "passive"))
    )
    (net (code "12") (name "CAN_N") (class "Default")
      (node (ref "CAN") (pin "2") (pinfunction "2_2") (pintype "bidirectional"))
      (node (ref "L2") (pin "3") (pinfunction "3_3") (pintype "passive"))
      (node (ref "SJ1") (pin "1") (pinfunction "1_1") (pintype "passive"))
    )
    (net (code "13") (name "CAN_P") (class "Default")
      (node (ref "CAN") (pin "1") (pinfunction "1_1") (pintype "bidirectional"))
      (node (ref "L2") (pin "4") (pinfunction "4_4") (pintype "passive"))
      (node (ref "R16") (pin "1") (pinfunction "1_1") (pintype "passive"))
    )
    (net (code "14") (name "CAN_RX") (class "Default")
      (node (ref "U1") (pin "2") (pinfunction "GPIO0_2") (pintype "bidirectional"))
      (node (ref "U3") (pin "4") (pinfunction "RXD_4") (pintype "output"))
    )
    (net (code "15") (name "CAN_TX") (class "Default")
      (node (ref "U1") (pin "3") (pinfunction "GPIO1_3") (pintype "bidirectional"))
      (node (ref "U3") (pin "1") (pinfunction "TXD_1") (pintype "input"))
    )
    (net (code "16") (name "E0_DIAG") (class "Default")
      (node (ref "U1") (pin "39") (pinfunction "GPIO27/ADC1_39") (pintype "bidirectional"))
      (node (ref "U7") (pin "11") (pinfunction "DIAG_11") (pintype "output"))
    )
    (net (code "17") (name "E0_DIR") (class "Default")
      (node (ref "R25") (pin "1") (pinfunction "1_1") (pintype "passive"))
      (node (ref "U1") (pin "32") (pinfunction "GPIO21_32") (pintype "bidirectional"))
    )
    (net (code "18") (name "E0_EN") (class "Default")
      (node (ref "R23") (pin "2") (pinfunction "2_2") (pintype "passive"))
      (node (ref "U1") (pin "40") (pinfunction "GPIO28/ADC2_40") (pintype "bidirectional"))
    )
    (net (code "19") (name "E0_STEP") (class "Default")
      (node (ref "R24") (pin "1") (pinfunction "1_1") (pintype "passive"))
      (node (ref "U1") (pin "36") (pinfunction "GPIO24_36") (pintype "bidirectional"))
    )
    (net (code "20") (name "E0_UART") (class "Default")
      (node (ref "R22") (pin "2") (pinfunction "2_2") (pintype "passive"))
      (node (ref "U1") (pin "37") (pinfunction "GPIO25_37") (pintype "bidirectional"))
      (node (ref "U7") (pin "14") (pinfunction "PDN_UART_14") (pintype "bidirectional"))
    )
    (net (code "21") (name "ENDSTOP_X") (class "Default")
      (node (ref "R40") (pin "1") (pinfunction "1_1") (pintype "passive"))
      (node (ref "U1") (pin "9") (pinfunction "GPIO7_9") (pintype "bidirectional"))
    )
    (net (code "22") (name "FAN0") (class "Default")
      (node (ref "R44") (pin "2") (pinfunction "2_2") (pintype "passive"))
      (node (ref "R45") (pin "2") (pinfunction "2_2") (pintype "passive"))
      (node (ref "U1") (pin "11") (pinfunction "GPIO8_11") (pintype "bidirectional"))
    )
    (net (code "23") (name "FAN1") (class "Default")
      (node (ref "R46") (pin "2") (pinfunction "2_2") (pintype "passive"))
      (node (ref "R47") (pin "2") (pinfunction "2_2") (pintype "passive"))
      (node (ref "U1") (pin "12") (pinfunction "GPIO9_12") (pintype "bidirectional"))
    )
    (net (code "24") (name "FAN2") (class "Default")
      (node (ref "R48") (pin "2") (pinfunction "2_2") (pintype "passive"))
      (node (ref "R49") (pin "2") (pinfunction "2_2") (pintype "passive"))
      (node (ref "U1") (pin "13") (pinfunction "GPIO10_13") (pintype "bidirectional"))
    )
    (net (code "25") (name "GND") (class "Default")
      (node (ref "BOOT") (pin "1") (pinfunction "1_1") (pintype "bidirectional"))
      (node (ref "C1") (pin "2") (pinfunction "2_2") (pintype "passive"))
      (node (ref "C10") (pin "2") (pinfunction "2_2") (pintype "passive"))
      (node (ref "C11") (pin "2") (pinfunction "2_2") (pintype "passive"))
      (node (ref "C12") (pin "2") (pinfunction "2_2") (pintype "passive"))
      (node (ref "C13") (pin "2") (pinfunction "2_2") (pintype "passive"))
      (node (ref "C14") (pin "2") (pinfunction "2_2") (pintype "passive"))
      (node (ref "C15") (pin "2") (pinfunction "2_2") (pintype "passive"))
      (node (ref "C16") (pin "2") (pinfunction "2_2") (pintype "passive"))
      (node (ref "C17") (pin "2") (pinfunction "2_2") (pintype "passive"))
      (node (ref "C18") (pin "2") (pinfunction "2_2") (pintype "passive"))
      (node (ref "C19") (pin "2") (pinfunction "2_2") (pintype "passive"))
      (node (ref "C2") (pin "1") (pinfunction "1_1") (pintype "passive"))
      (node (ref "C21") (pin "2") (pinfunction "2_2") (pintype "passive"))
      (node (ref "C22") (pin "2") (pinfunction "2_2") (pintype "passive"))
      (node (ref "C24") (pin "2") (pinfunction "2_2") (pintype "passive"))
      (node (ref "C25") (pin "1") (pinfunction "1_1") (pintype "passive"))
      (node (ref "C26") (pin "2") (pinfunction "2_2") (pintype "passive"))
      (node (ref "C27") (pin "2") (pinfunction "2_2") (pintype "passive"))
      (node (ref "C3") (pin "2") (pinfunction "2_2") (pintype "passive"))
      (node (ref "C30") (pin "1") (pinfunction "1_1") (pintype "passive"))
      (node (ref "C31") (pin "1") (pinfunction "1_1") (pintype "passive"))
      (node (ref "C32") (pin "1") (pinfunction "1_1") (pintype "passive"))
      (node (ref "C33") (pin "-") (pinfunction "-_-") (pintype "passive"))
      (node (ref "C34") (pin "2") (pinfunction "2_2") (pintype "passive"))
      (node (ref "C38") (pin "2") (pinfunction "2_2") (pintype "passive"))
      (node (ref "C39") (pin "2") (pinfunction "2_2") (pintype "passive"))
      (node (ref "C4") (pin "2") (pinfunction "2_2") (pintype "passive"))
      (node (ref "C40") (pin "2") (pinfunction "2_2") (pintype "passive"))
      (node (ref "C42") (pin "2") (pinfunction "2_2") (pintype "passive"))
      (node (ref "C43") (pin "2") (pinfunction "2_2") (pintype "passive"))
      (node (ref "C44") (pin "2") (pinfunction "2_2") (pintype "passive"))
      (node (ref "C45") (pin "2") (pinfunction "2_2") (pintype "passive"))
      (node (ref "C5") (pin "2") (pinfunction "2_2") (pintype "passive"))
      (node (ref "C6") (pin "2") (pinfunction "2_2") (pintype "passive"))
      (node (ref "C7") (pin "2") (pinfunction "2_2") (pintype "passive"))
      (node (ref "C8") (pin "2") (pinfunction "2_2") (pintype "passive"))
      (node (ref "C9") (pin "2") (pinfunction "2_2") (pintype "passive"))
      (node (ref "D2") (pin "2") (pinfunction "GND_2") (pintype "power_in"))
      (node (ref "D3") (pin "C") (pinfunction "C_C") (pintype "passive"))
      (node (ref "D4") (pin "1") (pinfunction "1_1") (pintype "passive"))
      (node (ref "D6") (pin "1") (pinfunction "1_1") (pintype "passive"))
      (node (ref "D7") (pin "1") (pinfunction "1_1") (pintype "passive"))
      (node (ref "D8") (pin "1") (pinfunction "1_1") (pintype "passive"))
      (node (ref "D9") (pin "C") (pinfunction "C_C") (pintype "passive"))
      (node (ref "EX-") (pin "1") (pinfunction "1_1") (pintype "bidirectional"))
      (node (ref "GND") (pin "P$1") (pinfunction "1_P$1") (pintype "bidirectional"))
      (node (ref "J2") (pin "2") (pinfunction "2_2") (pintype "bidirectional"))
      (node (ref "J3") (pin "3") (pinfunction "3_3") (pintype "passive"))
      (node (ref "M1") (pin "P$1") (pinfunction "S_P$1") (pintype "passive"))
      (node (ref "M1") (pin "P$2") (pinfunction "S_P$2") (pintype "passive"))
      (node (ref "M1") (pin "P$3") (pinfunction "S_P$3") (pintype "passive"))
      (node (ref "M2") (pin "2") (pinfunction "S_2") (pintype "passive"))
      (node (ref "M3") (pin "2") (pinfunction "S_2") (pintype "passive"))
      (node (ref "M4") (pin "2") (pinfunction "S_2") (pintype "passive"))
      (node (ref "P1") (pin "1") (pinfunction "GND_1") (pintype "bidirectional"))
      (node (ref "P2") (pin "2") (pinfunction "GND_2") (pintype "input"))
      (node (ref "R22") (pin "1") (pinfunction "1_1") (pintype "passive"))
      (node (ref "R26") (pin "1") (pinfunction "1_1") (pintype "passive"))
      (node (ref "R27") (pin "1") (pinfunction "1_1") (pintype "passive"))
      (node (ref "R30") (pin "1") (pinfunction "1_1") (pintype "passive"))
      (node (ref "R37") (pin "1") (pinfunction "1_1") (pintype "passive"))
      (node (ref "R45") (pin "1") (pinfunction "1_1") (pintype "passive"))
      (node (ref "R47") (pin "1") (pinfunction "1_1") (pintype "passive"))
      (node (ref "R49") (pin "1") (pinfunction "1_1") (pintype "passive"))
      (node (ref "R6") (pin "1") (pinfunction "1_1") (pintype "passive"))
      (node (ref "R9") (pin "1") (pinfunction "1_1") (pintype "passive"))
      (node (ref "RST") (pin "1") (pinfunction "1_1") (pintype "bidirectional"))
      (node (ref "U1") (pin "19") (pinfunction "TESTEN_19") (pintype "passive"))
      (node (ref "U1") (pin "57") (pinfunction "GND_57") (pintype "passive"))
      (node (ref "U2") (pin "4") (pinfunction "GND_4") (pintype "passive"))
      (node (ref "U3") (pin "2") (pinfunction "GND_2") (pintype "power_in"))
      (node (ref "U3") (pin "8") (pinfunction "STBY_8") (pintype "input"))
      (node (ref "U5") (pin "2") (pinfunction "GND_2") (pintype "bidirectional"))
      (node (ref "U5") (pin "4") (pinfunction "GND1_4") (pintype "bidirectional"))
      (node (ref "U5") (pin "5") (pinfunction "GND2_5") (pintype "bidirectional"))
      (node (ref "U6") (pin "3") (pinfunction "GND_3") (pintype "power_in"))
      (node (ref "U7") (pin "13") (pinfunction "CLK_13") (pintype "input"))
      (node (ref "U7") (pin "18") (pinfunction "GND_18") (pintype "power_in"))
      (node (ref "U7") (pin "29") (pinfunction "EPAD_29") (pintype "passive"))
      (node (ref "U7") (pin "3") (pinfunction "GND_2_3") (pintype "power_in"))
      (node (ref "U7") (pin "7") (pinfunction "SPREAD_7") (pintype "input"))
      (node (ref "USB") (pin "1") (pinfunction "GND_1") (pintype "power_in"))
      (node (ref "USB") (pin "12") (pinfunction "GND2_12") (pintype "power_in"))
      (node (ref "USB") (pin "13") (pinfunction "SHLD_13") (pintype "passive"))
      (node (ref "USB") (pin "14") (pinfunction "SHLD_14") (pintype "passive"))
      (node (ref "USB") (pin "15") (pinfunction "SHLD_15") (pintype "passive"))
      (node (ref "USB") (pin "16") (pinfunction "SHLD_16") (pintype "passive"))
      (node (ref "USB") (pin "18") (pinfunction "SHLD_18") (pintype "passive"))
      (node (ref "USB") (pin "19") (pinfunction "SHLD_19") (pintype "passive"))
      (node (ref "USB") (pin "20") (pinfunction "SHLD_20") (pintype "passive"))
      (node (ref "USB") (pin "21") (pinfunction "SHLD_21") (pintype "passive"))
      (node (ref "USB") (pin "24") (pinfunction "SHLD_24") (pintype "passive"))
      (node (ref "USB") (pin "25") (pinfunction "SHLD_25") (pintype "passive"))
      (node (ref "USB") (pin "26") (pinfunction "SHLD_26") (pintype "passive"))
      (node (ref "USB") (pin "27") (pinfunction "SHLD_27") (pintype "passive"))
      (node (ref "USB") (pin "28") (pinfunction "SHLD_28") (pintype "passive"))
      (node (ref "USB") (pin "29") (pinfunction "SHLD_29") (pintype "passive"))
      (node (ref "USB") (pin "37") (pinfunction "SHLD_37") (pintype "passive"))
      (node (ref "USB") (pin "39") (pinfunction "SHLD_39") (pintype "passive"))
      (node (ref "USB") (pin "41") (pinfunction "SHLD_41") (pintype "passive"))
      (node (ref "USB") (pin "43") (pinfunction "SHLD_43") (pintype "passive"))
      (node (ref "X1") (pin "P$2") (pinfunction "GND_P$2") (pintype "bidirectional"))
      (node (ref "X1") (pin "P$4") (pinfunction "GND_P$4") (pintype "bidirectional"))
    )
    (net (code "26") (name "HE0") (class "Default")
      (node (ref "R37") (pin "2") (pinfunction "2_2") (pintype "passive"))
      (node (ref "U1") (pin "31") (pinfunction "GPIO20_31") (pintype "bidirectional"))
      (node (ref "U6") (pin "2") (pinfunction "A_2") (pintype "input"))
    )
    (net (code "27") (name "HE0_PWR") (class "Default")
      (node (ref "J3") (pin "1") (pinfunction "1_1") (pintype "passive"))
      (node (ref "M1") (pin "P$5") (pinfunction "D_P$5") (pintype "passive"))
      (node (ref "M1") (pin "P$6") (pinfunction "D_P$6") (pintype "passive"))
      (node (ref "M1") (pin "P$7") (pinfunction "D_P$7") (pintype "passive"))
      (node (ref "M1") (pin "P$8") (pinfunction "D_P$8") (pintype "passive"))
      (node (ref "M1") (pin "P$9") (pinfunction "D_P$9") (pintype "passive"))
    )
    (net (code "28") (name "I2C_SCL") (class "Default")
      (node (ref "IO23") (pin "P$1") (pinfunction "1_P$1") (pintype "bidirectional"))
      (node (ref "U1") (pin "35") (pinfunction "GPIO23_35") (pintype "bidirectional"))
    )
    (net (code "29") (name "I2C_SDA") (class "Default")
      (node (ref "IO22") (pin "P$1") (pinfunction "1_P$1") (pintype "bidirectional"))
      (node (ref "U1") (pin "34") (pinfunction "GPIO22_34") (pintype "bidirectional"))
    )
    (net (code "30") (name "Net-(BOOT-Pad2)") (class "Default")
      (node (ref "BOOT") (pin "2") (pinfunction "2_2") (pintype "bidirectional"))
      (node (ref "R12") (pin "2") (pinfunction "2_2") (pintype "passive"))
    )
    (net (code "31") (name "Net-(C23-Pad1)") (class "Default")
      (node (ref "C23") (pin "1") (pinfunction "1_1") (pintype "passive"))
      (node (ref "R7") (pin "1") (pinfunction "1_1") (pintype "passive"))
      (node (ref "R8") (pin "2") (pinfunction "2_2") (pintype "passive"))
    )
    (net (code "32") (name "Net-(D1-A)") (class "Default")
      (node (ref "D1") (pin "2") (pinfunction "A_2") (pintype "passive"))
      (node (ref "F1") (pin "1") (pinfunction "1_1") (pintype "passive"))
    )
    (net (code "33") (name "Net-(D2-I{slash}O1)") (class "Default")
      (node (ref "D2") (pin "1") (pinfunction "I/O1_2_1") (pintype "bidirectional"))
      (node (ref "D2") (pin "6") (pinfunction "I/O1_6") (pintype "bidirectional"))
      (node (ref "R10") (pin "1") (pinfunction "1_1") (pintype "passive"))
      (node (ref "USB") (pin "6") (pinfunction "AD+_6") (pintype "passive"))
      (node (ref "USB") (pin "7") (pinfunction "BD+_7") (pintype "passive"))
    )
    (net (code "34") (name "Net-(D2-I{slash}O2)") (class "Default")
      (node (ref "D2") (pin "3") (pinfunction "I/O2_2_3") (pintype "bidirectional"))
      (node (ref "D2") (pin "4") (pinfunction "I/O2_4") (pintype "bidirectional"))
      (node (ref "R11") (pin "1") (pinfunction "1_1") (pintype "passive"))
      (node (ref "USB") (pin "5") (pinfunction "BD-_5") (pintype "passive"))
      (node (ref "USB") (pin "8") (pinfunction "AD-_8") (pintype "passive"))
    )
    (net (code "35") (name "Net-(D2-VBUS)") (class "Default")
      (node (ref "D2") (pin "5") (pinfunction "VBUS_5") (pintype "power_in"))
      (node (ref "F1") (pin "2") (pinfunction "2_2") (pintype "passive"))
      (node (ref "SJ3") (pin "1") (pinfunction "1_1") (pintype "passive"))
    )
    (net (code "36") (name "Net-(D3-PadA)") (class "Default")
      (node (ref "D3") (pin "A") (pinfunction "A_A") (pintype "passive"))
      (node (ref "R15") (pin "1") (pinfunction "1_1") (pintype "passive"))
    )
    (net (code "37") (name "Net-(D4-Pad3)") (class "Default")
      (node (ref "D4") (pin "3") (pinfunction "3_3") (pintype "passive"))
      (node (ref "R35") (pin "2") (pinfunction "2_2") (pintype "passive"))
      (node (ref "R36") (pin "1") (pinfunction "1_1") (pintype "passive"))
    )
    (net (code "38") (name "Net-(D9-PadA)") (class "Default")
      (node (ref "D9") (pin "A") (pinfunction "A_A") (pintype "passive"))
      (node (ref "R28") (pin "1") (pinfunction "1_1") (pintype "passive"))
    )
    (net (code "39") (name "Net-(EX--Pad2)") (class "Default")
      (node (ref "EX-") (pin "2") (pinfunction "2_2") (pintype "bidirectional"))
      (node (ref "R40") (pin "2") (pinfunction "2_2") (pintype "passive"))
      (node (ref "R41") (pin "2") (pinfunction "2_2") (pintype "passive"))
    )
    (net (code "40") (name "Net-(FAN2-Pad2)") (class "Default")
      (node (ref "FAN2") (pin "2") (pinfunction "2_2") (pintype "bidirectional"))
      (node (ref "FAN3") (pin "2") (pinfunction "2_2") (pintype "bidirectional"))
    )
    (net (code "41") (name "Net-(J3-Pad4)") (class "Default")
      (node (ref "J3") (pin "4") (pinfunction "4_4") (pintype "passive"))
      (node (ref "R33") (pin "1") (pinfunction "1_1") (pintype "passive"))
      (node (ref "R34") (pin "1") (pinfunction "1_1") (pintype "passive"))
      (node (ref "R35") (pin "1") (pinfunction "1_1") (pintype "passive"))
    )
    (net (code "42") (name "Net-(M1-G)") (class "Default")
      (node (ref "M1") (pin "P$4") (pinfunction "G_P$4") (pintype "passive"))
      (node (ref "R31") (pin "1") (pinfunction "1_1") (pintype "passive"))
    )
    (net (code "43") (name "Net-(M2-D)") (class "Default")
      (node (ref "FAN0") (pin "1") (pinfunction "1_1") (pintype "bidirectional"))
      (node (ref "M2") (pin "3") (pinfunction "D_3") (pintype "passive"))
    )
    (net (code "44") (name "Net-(M2-G)") (class "Default")
      (node (ref "D6") (pin "3") (pinfunction "3_3") (pintype "passive"))
      (node (ref "M2") (pin "1") (pinfunction "G_1") (pintype "passive"))
      (node (ref "R44") (pin "1") (pinfunction "1_1") (pintype "passive"))
    )
    (net (code "45") (name "Net-(M3-D)") (class "Default")
      (node (ref "FAN1") (pin "1") (pinfunction "1_1") (pintype "bidirectional"))
      (node (ref "M3") (pin "3") (pinfunction "D_3") (pintype "passive"))
    )
    (net (code "46") (name "Net-(M3-G)") (class "Default")
      (node (ref "D7") (pin "3") (pinfunction "3_3") (pintype "passive"))
      (node (ref "M3") (pin "1") (pinfunction "G_1") (pintype "passive"))
      (node (ref "R46") (pin "1") (pinfunction "1_1") (pintype "passive"))
    )
    (net (code "47") (name "Net-(M4-D)") (class "Default")
      (node (ref "FAN2") (pin "1") (pinfunction "1_1") (pintype "bidirectional"))
      (node (ref "FAN3") (pin "1") (pinfunction "1_1") (pintype "bidirectional"))
      (node (ref "M4") (pin "3") (pinfunction "D_3") (pintype "passive"))
    )
    (net (code "48") (name "Net-(M4-G)") (class "Default")
      (node (ref "D8") (pin "3") (pinfunction "3_3") (pintype "passive"))
      (node (ref "M4") (pin "1") (pinfunction "G_1") (pintype "passive"))
      (node (ref "R48") (pin "1") (pinfunction "1_1") (pintype "passive"))
    )
    (net (code "49") (name "Net-(P1-BOOT)") (class "Default")
      (node (ref "C20") (pin "1") (pinfunction "1_1") (pintype "passive"))
      (node (ref "P1") (pin "6") (pinfunction "BOOT_6") (pintype "bidirectional"))
    )
    (net (code "50") (name "Net-(P1-EN)") (class "Default")
      (node (ref "P1") (pin "5") (pinfunction "EN_5") (pintype "bidirectional"))
      (node (ref "R5") (pin "1") (pinfunction "1_1") (pintype "passive"))
      (node (ref "R6") (pin "2") (pinfunction "2_2") (pintype "passive"))
    )
    (net (code "51") (name "Net-(P1-FB)") (class "Default")
      (node (ref "C23") (pin "2") (pinfunction "2_2") (pintype "passive"))
      (node (ref "P1") (pin "4") (pinfunction "FB_4") (pintype "bidirectional"))
      (node (ref "R8") (pin "1") (pinfunction "1_1") (pintype "passive"))
      (node (ref "R9") (pin "2") (pinfunction "2_2") (pintype "passive"))
    )
    (net (code "52") (name "Net-(P1-SW)") (class "Default")
      (node (ref "C20") (pin "2") (pinfunction "2_2") (pintype "passive"))
      (node (ref "L1") (pin "1") (pinfunction "1_1") (pintype "bidirectional"))
      (node (ref "P1") (pin "2") (pinfunction "SW_2") (pintype "bidirectional"))
    )
    (net (code "53") (name "Net-(R1-Pad1)") (class "Default")
      (node (ref "R1") (pin "1") (pinfunction "1_1") (pintype "passive"))
      (node (ref "R2") (pin "2") (pinfunction "2_2") (pintype "passive"))
    )
    (net (code "54") (name "Net-(R16-Pad2)") (class "Default")
      (node (ref "R16") (pin "2") (pinfunction "2_2") (pintype "passive"))
      (node (ref "SJ1") (pin "2") (pinfunction "2_2") (pintype "passive"))
    )
    (net (code "55") (name "Net-(R34-Pad2)") (class "Default")
      (node (ref "R34") (pin "2") (pinfunction "2_2") (pintype "passive"))
      (node (ref "SJ2") (pin "1") (pinfunction "1_1") (pintype "passive"))
    )
    (net (code "56") (name "Net-(U1-GPIO2)") (class "Default")
      (node (ref "R28") (pin "2") (pinfunction "2_2") (pintype "passive"))
      (node (ref "U1") (pin "4") (pinfunction "GPIO2_4") (pintype "bidirectional"))
    )
    (net (code "57") (name "Net-(U3-CANH)") (class "Default")
      (node (ref "L2") (pin "1") (pinfunction "1_1") (pintype "passive"))
      (node (ref "U3") (pin "7") (pinfunction "CANH_7") (pintype "output"))
    )
    (net (code "58") (name "Net-(U3-CANL)") (class "Default")
      (node (ref "L2") (pin "2") (pinfunction "2_2") (pintype "passive"))
      (node (ref "U3") (pin "6") (pinfunction "CANL_6") (pintype "output"))
    )
    (net (code "59") (name "Net-(U6-Y)") (class "Default")
      (node (ref "R30") (pin "2") (pinfunction "2_2") (pintype "passive"))
      (node (ref "R31") (pin "2") (pinfunction "2_2") (pintype "passive"))
      (node (ref "U6") (pin "4") (pinfunction "Y_4") (pintype "output"))
    )
    (net (code "60") (name "Net-(U7-5VOUT)") (class "Default")
      (node (ref "C32") (pin "2") (pinfunction "2_2") (pintype "passive"))
      (node (ref "U7") (pin "8") (pinfunction "5VOUT_8") (pintype "output"))
    )
    (net (code "61") (name "Net-(U7-CPI)") (class "Default")
      (node (ref "C28") (pin "1") (pinfunction "1_1") (pintype "passive"))
      (node (ref "U7") (pin "5") (pinfunction "CPI_5") (pintype "input"))
    )
    (net (code "62") (name "Net-(U7-CPO)") (class "Default")
      (node (ref "C28") (pin "2") (pinfunction "2_2") (pintype "passive"))
      (node (ref "U7") (pin "4") (pinfunction "CPO_4") (pintype "output"))
    )
    (net (code "63") (name "Net-(U7-DIR)") (class "Default")
      (node (ref "R25") (pin "2") (pinfunction "2_2") (pintype "passive"))
      (node (ref "U7") (pin "19") (pinfunction "DIR_19") (pintype "input"))
    )
    (net (code "64") (name "Net-(U7-ENN)") (class "Default")
      (node (ref "R21") (pin "2") (pinfunction "2_2") (pintype "passive"))
      (node (ref "R23") (pin "1") (pinfunction "1_1") (pintype "passive"))
      (node (ref "U7") (pin "2") (pinfunction "ENN_2") (pintype "input"))
    )
    (net (code "65") (name "Net-(U7-STEP)") (class "Default")
      (node (ref "R24") (pin "2") (pinfunction "2_2") (pintype "passive"))
      (node (ref "U7") (pin "16") (pinfunction "STEP_16") (pintype "input"))
    )
    (net (code "66") (name "Net-(U7-VCP)") (class "Default")
      (node (ref "C29") (pin "2") (pinfunction "2_2") (pintype "passive"))
      (node (ref "U7") (pin "6") (pinfunction "VCP_6") (pintype "power_in"))
    )
    (net (code "67") (name "Net-(X1-P2)") (class "Default")
      (node (ref "C2") (pin "2") (pinfunction "2_2") (pintype "passive"))
      (node (ref "R3") (pin "1") (pinfunction "1_1") (pintype "passive"))
      (node (ref "X1") (pin "P$3") (pinfunction "P2_P$3") (pintype "bidirectional"))
    )
    (net (code "68") (name "OSC_IN") (class "Default")
      (node (ref "C1") (pin "1") (pinfunction "1_1") (pintype "passive"))
      (node (ref "R4") (pin "2") (pinfunction "2_2") (pintype "passive"))
      (node (ref "U1") (pin "20") (pinfunction "XIN_20") (pintype "passive"))
      (node (ref "X1") (pin "P$1") (pinfunction "P1_P$1") (pintype "bidirectional"))
    )
    (net (code "69") (name "OSC_OUT") (class "Default")
      (node (ref "R3") (pin "2") (pinfunction "2_2") (pintype "passive"))
      (node (ref "R4") (pin "1") (pinfunction "1_1") (pintype "passive"))
      (node (ref "U1") (pin "21") (pinfunction "XOUT_21") (pintype "output"))
    )
    (net (code "70") (name "QSPI_SCK") (class "Default")
      (node (ref "U1") (pin "52") (pinfunction "QSPI_SCLK_52") (pintype "passive"))
      (node (ref "U2") (pin "6") (pinfunction "CLK_6") (pintype "passive"))
    )
    (net (code "71") (name "QSPI_SD0") (class "Default")
      (node (ref "U1") (pin "53") (pinfunction "QSPI_SD0_53") (pintype "bidirectional"))
      (node (ref "U2") (pin "5") (pinfunction "DI_(IO0)_5") (pintype "passive"))
    )
    (net (code "72") (name "QSPI_SD1") (class "Default")
      (node (ref "U1") (pin "55") (pinfunction "QSPI_SD1_55") (pintype "bidirectional"))
      (node (ref "U2") (pin "2") (pinfunction "DO_(IO1)_2") (pintype "passive"))
    )
    (net (code "73") (name "QSPI_SD2") (class "Default")
      (node (ref "U1") (pin "54") (pinfunction "QSPI_SD2_54") (pintype "bidirectional"))
      (node (ref "U2") (pin "3") (pinfunction "/WP_(IO2)_3") (pintype "passive"))
    )
    (net (code "74") (name "QSPI_SD3") (class "Default")
      (node (ref "U1") (pin "51") (pinfunction "QSPI_SD3_51") (pintype "bidirectional"))
      (node (ref "U2") (pin "7") (pinfunction "/RESET_(IO3)_7") (pintype "passive"))
    )
    (net (code "75") (name "QSPI_SS") (class "Default")
      (node (ref "R12") (pin "1") (pinfunction "1_1") (pintype "passive"))
      (node (ref "R13") (pin "1") (pinfunction "1_1") (pintype "passive"))
      (node (ref "U1") (pin "56") (pinfunction "QSPI_SS_N_56") (pintype "passive"))
      (node (ref "U2") (pin "1") (pinfunction "/CS_1") (pintype "passive"))
    )
    (net (code "76") (name "RESET") (class "Default")
      (node (ref "C25") (pin "2") (pinfunction "2_2") (pintype "passive"))
      (node (ref "R14") (pin "1") (pinfunction "1_1") (pintype "passive"))
      (node (ref "RST") (pin "2") (pinfunction "2_2") (pintype "bidirectional"))
      (node (ref "U1") (pin "26") (pinfunction "RUN_26") (pintype "passive"))
    )
    (net (code "77") (name "SPI0_CS") (class "Default")
      (node (ref "IO17") (pin "P$1") (pinfunction "1_P$1") (pintype "bidirectional"))
      (node (ref "U1") (pin "28") (pinfunction "GPIO17_28") (pintype "bidirectional"))
    )
    (net (code "78") (name "SPI0_MISO") (class "Default")
      (node (ref "IO16") (pin "P$1") (pinfunction "1_P$1") (pintype "bidirectional"))
      (node (ref "U1") (pin "27") (pinfunction "GPIO16_27") (pintype "bidirectional"))
    )
    (net (code "79") (name "SPI0_MOSI") (class "Default")
      (node (ref "IO19") (pin "P$1") (pinfunction "1_P$1") (pintype "bidirectional"))
      (node (ref "U1") (pin "30") (pinfunction "GPIO19_30") (pintype "bidirectional"))
    )
    (net (code "80") (name "SPI0_SCK") (class "Default")
      (node (ref "IO18") (pin "P$1") (pinfunction "1_P$1") (pintype "bidirectional"))
      (node (ref "U1") (pin "29") (pinfunction "GPIO18_29") (pintype "bidirectional"))
    )
    (net (code "81") (name "SPI1_CS") (class "Default")
      (node (ref "R19") (pin "1") (pinfunction "1_1") (pintype "passive"))
      (node (ref "U1") (pin "16") (pinfunction "GPIO13_16") (pintype "bidirectional"))
      (node (ref "U5") (pin "7") (pinfunction "~{CS}_7") (pintype "bidirectional"))
    )
    (net (code "82") (name "SPI1_MISO") (class "Default")
      (node (ref "R18") (pin "1") (pinfunction "1_1") (pintype "passive"))
      (node (ref "U1") (pin "15") (pinfunction "GPIO12_15") (pintype "bidirectional"))
      (node (ref "U5") (pin "12") (pinfunction "SDO/ALT_ADDRESS_12") (pintype "bidirectional"))
    )
    (net (code "83") (name "SPI1_MOSI") (class "Default")
      (node (ref "R17") (pin "1") (pinfunction "1_1") (pintype "passive"))
      (node (ref "U1") (pin "18") (pinfunction "GPIO15_18") (pintype "bidirectional"))
      (node (ref "U5") (pin "13") (pinfunction "SDA/SDI/SDIO_13") (pintype "bidirectional"))
    )
    (net (code "84") (name "SPI1_SCK") (class "Default")
      (node (ref "R20") (pin "1") (pinfunction "1_1") (pintype "passive"))
      (node (ref "U1") (pin "17") (pinfunction "GPIO14_17") (pintype "bidirectional"))
      (node (ref "U5") (pin "14") (pinfunction "SCL/SCLK_14") (pintype "bidirectional"))
    )
    (net (code "85") (name "SWCLK") (class "Default")
      (node (ref "SWCLK") (pin "P$1") (pinfunction "1_P$1") (pintype "bidirectional"))
      (node (ref "U1") (pin "24") (pinfunction "SWCLK_24") (pintype "passive"))
    )
    (net (code "86") (name "SWDIO") (class "Default")
      (node (ref "SWDIO") (pin "P$1") (pinfunction "1_P$1") (pintype "bidirectional"))
      (node (ref "U1") (pin "25") (pinfunction "SWDIO_25") (pintype "passive"))
    )
    (net (code "87") (name "TH0") (class "Default")
      (node (ref "C40") (pin "1") (pinfunction "1_1") (pintype "passive"))
      (node (ref "R36") (pin "2") (pinfunction "2_2") (pintype "passive"))
      (node (ref "U1") (pin "38") (pinfunction "GPIO26/ADC0_38") (pintype "bidirectional"))
    )
    (net (code "88") (name "USB_N") (class "Default")
      (node (ref "IO1") (pin "P$1") (pinfunction "1_P$1") (pintype "bidirectional"))
      (node (ref "R11") (pin "2") (pinfunction "2_2") (pintype "passive"))
      (node (ref "U1") (pin "46") (pinfunction "USB_DM_46") (pintype "passive"))
    )
    (net (code "89") (name "USB_P") (class "Default")
      (node (ref "IO2") (pin "P$1") (pinfunction "1_P$1") (pintype "bidirectional"))
      (node (ref "R10") (pin "2") (pinfunction "2_2") (pintype "passive"))
      (node (ref "U1") (pin "47") (pinfunction "USB_DP_47") (pintype "passive"))
    )
    (net (code "90") (name "VBUS") (class "Default")
      (node (ref "SJ3") (pin "2") (pinfunction "2_2") (pintype "passive"))
      (node (ref "USB") (pin "11") (pinfunction "VBUS2_11") (pintype "power_in"))
      (node (ref "USB") (pin "2") (pinfunction "VBUS_2") (pintype "power_in"))
    )
    (net (code "91") (name "unconnected-(P2-NC-Pad4)") (class "Default")
      (node (ref "P2") (pin "4") (pinfunction "NC_4") (pintype "no_connect"))
    )
    (net (code "92") (name "unconnected-(U1-GPIO3-Pad5)") (class "Default")
      (node (ref "U1") (pin "5") (pinfunction "GPIO3_5") (pintype "bidirectional"))
    )
    (net (code "93") (name "unconnected-(U1-GPIO4-Pad6)") (class "Default")
      (node (ref "U1") (pin "6") (pinfunction "GPIO4_6") (pintype "bidirectional"))
    )
    (net (code "94") (name "unconnected-(U1-GPIO5-Pad7)") (class "Default")
      (node (ref "U1") (pin "7") (pinfunction "GPIO5_7") (pintype "bidirectional"))
    )
    (net (code "95") (name "unconnected-(U1-GPIO6-Pad8)") (class "Default")
      (node (ref "U1") (pin "8") (pinfunction "GPIO6_8") (pintype "bidirectional"))
    )
    (net (code "96") (name "unconnected-(U1-GPIO11-Pad14)") (class "Default")
      (node (ref "U1") (pin "14") (pinfunction "GPIO11_14") (pintype "bidirectional"))
    )
    (net (code "97") (name "unconnected-(U1-GPIO29{slash}ADC3-Pad41)") (class "Default")
      (node (ref "U1") (pin "41") (pinfunction "GPIO29/ADC3_41") (pintype "bidirectional"))
    )
    (net (code "98") (name "unconnected-(U5-INT1-Pad8)") (class "Default")
      (node (ref "U5") (pin "8") (pinfunction "INT1_8") (pintype "bidirectional"))
    )
    (net (code "99") (name "unconnected-(U5-INT2-Pad9)") (class "Default")
      (node (ref "U5") (pin "9") (pinfunction "INT2_9") (pintype "bidirectional"))
    )
    (net (code "100") (name "unconnected-(U5-NC-Pad10)") (class "Default")
      (node (ref "U5") (pin "10") (pinfunction "NC_10") (pintype "bidirectional"))
    )
    (net (code "101") (name "unconnected-(U5-RESERVED-Pad3)") (class "Default")
      (node (ref "U5") (pin "3") (pinfunction "RESERVED_3") (pintype "bidirectional"))
    )
    (net (code "102") (name "unconnected-(U5-RESERVED1-Pad11)") (class "Default")
      (node (ref "U5") (pin "11") (pinfunction "RESERVED1_11") (pintype "bidirectional"))
    )
    (net (code "103") (name "unconnected-(U6-NC-Pad1)") (class "Default")
      (node (ref "U6") (pin "1") (pinfunction "NC_1") (pintype "passive"))
    )
    (net (code "104") (name "unconnected-(U7-INDEX-Pad12)") (class "Default")
      (node (ref "U7") (pin "12") (pinfunction "INDEX_12") (pintype "output"))
    )
    (net (code "105") (name "unconnected-(U7-MS1_AD0-Pad9)") (class "Default")
      (node (ref "U7") (pin "9") (pinfunction "MS1_AD0_9") (pintype "input"))
    )
    (net (code "106") (name "unconnected-(U7-MS2_AD1-Pad10)") (class "Default")
      (node (ref "U7") (pin "10") (pinfunction "MS2_AD1_10") (pintype "input"))
    )
    (net (code "107") (name "unconnected-(U7-NC-Pad25)") (class "Default")
      (node (ref "U7") (pin "25") (pinfunction "NC_25") (pintype "no_connect"))
    )
    (net (code "108") (name "unconnected-(U7-STDBY-Pad20)") (class "Default")
      (node (ref "U7") (pin "20") (pinfunction "STDBY_20") (pintype "input"))
    )
    (net (code "109") (name "unconnected-(U7-VREF-Pad17)") (class "Default")
      (node (ref "U7") (pin "17") (pinfunction "VREF_17") (pintype "input"))
    )
    (net (code "110") (name "unconnected-(USB-CC1-Pad3)") (class "Default")
      (node (ref "USB") (pin "3") (pinfunction "CC1_3") (pintype "passive"))
    )
    (net (code "111") (name "unconnected-(USB-CC2-Pad9)") (class "Default")
      (node (ref "USB") (pin "9") (pinfunction "CC2_9") (pintype "passive"))
    )
    (net (code "112") (name "unconnected-(USB-SBU1-Pad10)") (class "Default")
      (node (ref "USB") (pin "10") (pinfunction "SBU1_10") (pintype "passive"))
    )
    (net (code "113") (name "unconnected-(USB-SBU2-Pad4)") (class "Default")
      (node (ref "USB") (pin "4") (pinfunction "SBU2_4") (pintype "passive"))
    )
  )
)
